# NerdvanaTaurus_FE.net
KiCad netlist of a schematic drawn in EasyEDA Pro
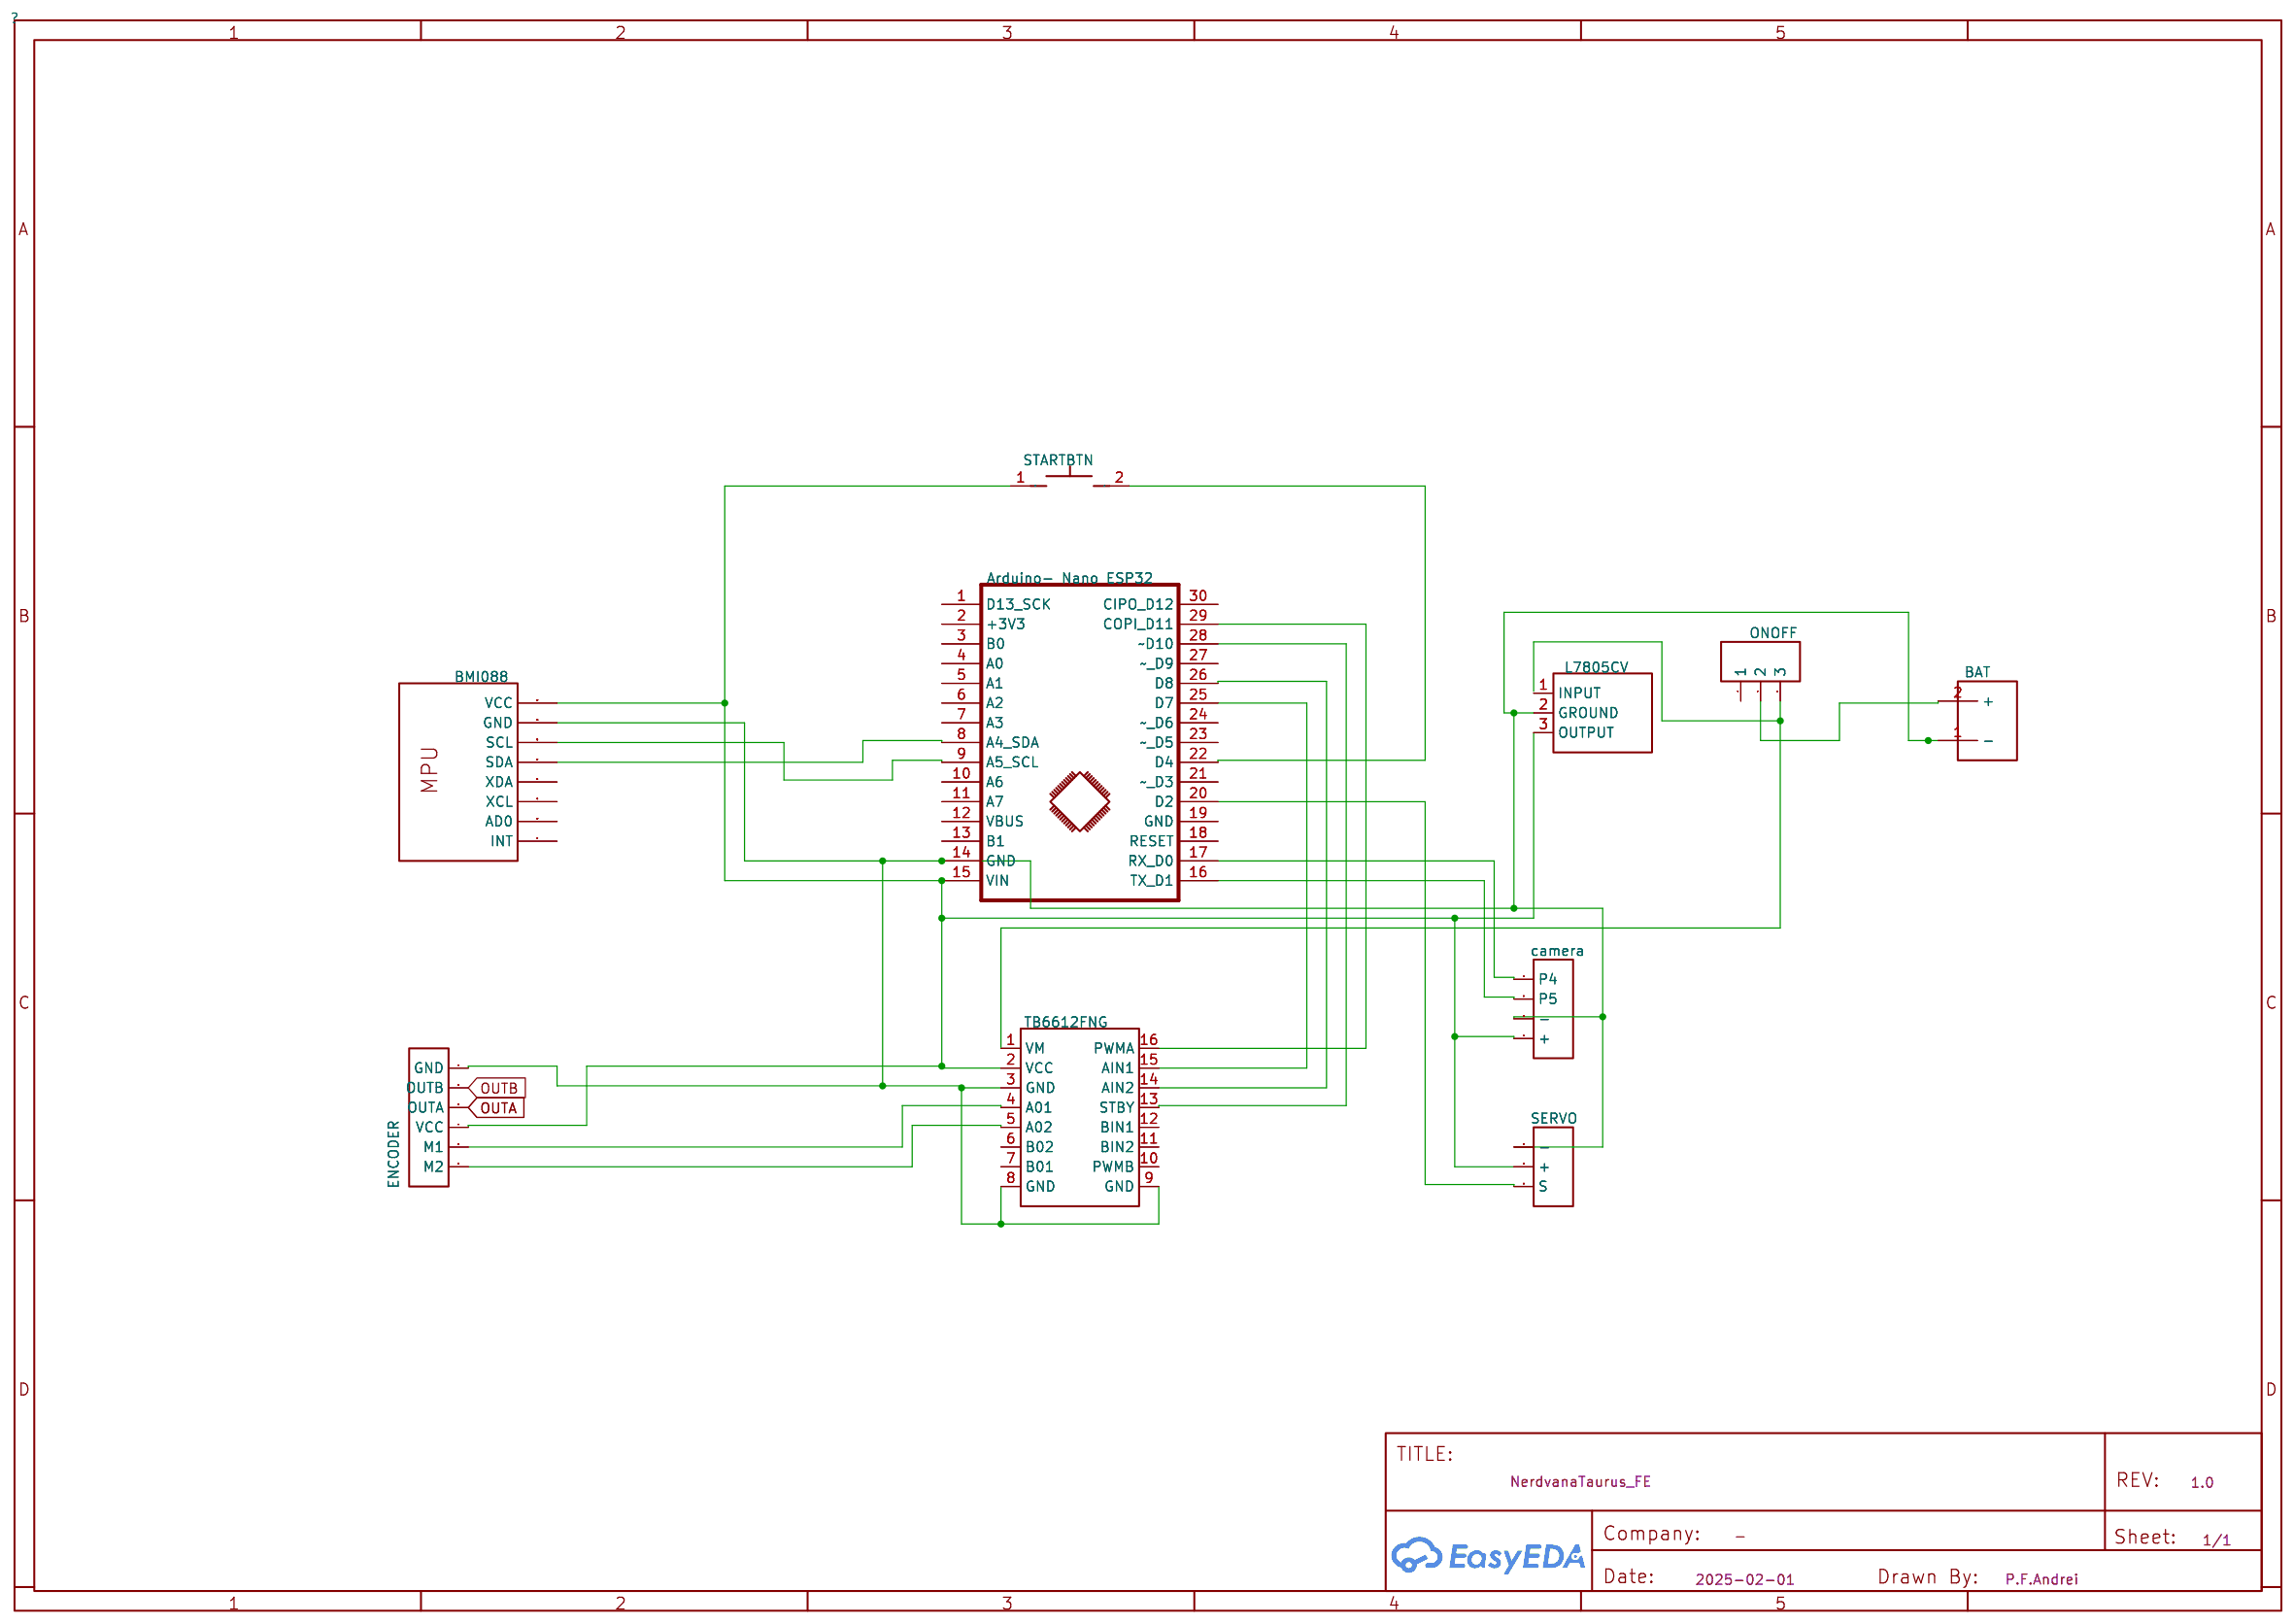
[diagram p0: schematic sheet]

(export (version "E")
  (design (tool "Eeschema 10.0.6"))
  (components
    (comp (ref "BAT1")
      (value "BAT")
      (fields (field (name "Contributor") "OFKLZ"))
      (libsource (lib "easyedapro") (part "BAT"))
    )
    (comp (ref "CAM1")
      (value "camera")
      (fields (field (name "Contributor") "LCEDA_Lib"))
      (libsource (lib "easyedapro") (part "camera"))
    )
    (comp (ref "H1")
      (value "ENCODER")
      (fields (field (name "Contributor") "LCEDA_Lib"))
      (libsource (lib "easyedapro") (part "ENCODER"))
    )
    (comp (ref "L1CV")
      (value "L7805CV")
      (fields (field (name "Manufacturer Part") "L7805CV带散热器") (field (name "Contributor") "LCSC"))
      (libsource (lib "easyedapro") (part "L7805CV"))
    )
    (comp (ref "M2")
      (value "BMI088")
      (fields (field (name "Contributor") "THE AS-Creation"))
      (libsource (lib "easyedapro") (part "MPU6050"))
    )
    (comp (ref "ONOFF1")
      (value "ONOFF")
      (fields (field (name "Contributor") "LCEDA_Lib"))
      (libsource (lib "easyedapro") (part "ONOFF"))
    )
    (comp (ref "SERVO1")
      (value "SERVO")
      (fields (field (name "Contributor") "LCEDA_Lib"))
      (libsource (lib "easyedapro") (part "SERVO"))
    )
    (comp (ref "START1")
      (value "STARTBTN")
      (fields (field (name "Manufacturer Part") "BUTTON2") (field (name "Contributor") "LCSC"))
      (libsource (lib "easyedapro") (part "STARTBTN"))
    )
    (comp (ref "U3")
      (value "Arduino- Nano ESP32")
      (fields
        (field (name "Manufacturer Part") "ABX00092")
        (field (name "Manufacturer") "Arduino")
        (field (name "Contributor") "jbdreamz365")
      )
      (libsource (lib "easyedapro") (part "Arduino® Nano ESP32"))
    )
    (comp (ref "U4")
      (value "TB6612FNG")
      (fields (field (name "Contributor") "sendme2vachan"))
      (libsource (lib "easyedapro") (part "TB6612FNG"))
    )
  )
  (nets
    (net (code "1") (name "Net-(BAT1-+)") (class "Default")
      (node (ref "BAT1") (pin "2") (pinfunction "+_2") (pintype "unspecified"))
      (node (ref "ONOFF1") (pin "2") (pinfunction "2_2") (pintype "input"))
    )
    (net (code "2") (name "Net-(BAT1--)") (class "Default")
      (node (ref "BAT1") (pin "1") (pinfunction "-_1") (pintype "unspecified"))
      (node (ref "CAM1") (pin "3") (pinfunction "-_3") (pintype "unspecified"))
      (node (ref "H1") (pin "1") (pinfunction "GND_1") (pintype "input"))
      (node (ref "L1CV") (pin "2") (pinfunction "GROUND_2") (pintype "unspecified"))
      (node (ref "M2") (pin "GND") (pinfunction "GND_GND") (pintype "unspecified"))
      (node (ref "SERVO1") (pin "1") (pinfunction "-_1") (pintype "input"))
      (node (ref "U3") (pin "14") (pinfunction "GND_14") (pintype "unspecified"))
      (node (ref "U4") (pin "3") (pinfunction "GND_3") (pintype "unspecified"))
      (node (ref "U4") (pin "8") (pinfunction "GND_8") (pintype "unspecified"))
      (node (ref "U4") (pin "9") (pinfunction "GND_9") (pintype "unspecified"))
    )
    (net (code "3") (name "Net-(CAM1-+)") (class "Default")
      (node (ref "CAM1") (pin "4") (pinfunction "+_4") (pintype "unspecified"))
      (node (ref "H1") (pin "4") (pinfunction "VCC_4") (pintype "input"))
      (node (ref "L1CV") (pin "3") (pinfunction "OUTPUT_3") (pintype "unspecified"))
      (node (ref "M2") (pin "VCC") (pinfunction "VCC_VCC") (pintype "unspecified"))
      (node (ref "SERVO1") (pin "2") (pinfunction "+_2") (pintype "input"))
      (node (ref "START1") (pin "1") (pinfunction "1_1") (pintype "unspecified"))
      (node (ref "U3") (pin "15") (pinfunction "VIN_15") (pintype "bidirectional"))
      (node (ref "U4") (pin "2") (pinfunction "VCC_2") (pintype "unspecified"))
    )
    (net (code "4") (name "Net-(CAM1-P4)") (class "Default")
      (node (ref "CAM1") (pin "1") (pinfunction "P4_1") (pintype "unspecified"))
      (node (ref "U3") (pin "17") (pinfunction "RX_D0_17") (pintype "bidirectional"))
    )
    (net (code "5") (name "Net-(CAM1-P5)") (class "Default")
      (node (ref "CAM1") (pin "2") (pinfunction "P5_2") (pintype "unspecified"))
      (node (ref "U3") (pin "16") (pinfunction "TX_D1_16") (pintype "bidirectional"))
    )
    (net (code "6") (name "Net-(H1-M1)") (class "Default")
      (node (ref "H1") (pin "5") (pinfunction "M1_5") (pintype "input"))
      (node (ref "U4") (pin "4") (pinfunction "A01_4") (pintype "unspecified"))
    )
    (net (code "7") (name "Net-(H1-M2)") (class "Default")
      (node (ref "H1") (pin "6") (pinfunction "M2_6") (pintype "input"))
      (node (ref "U4") (pin "5") (pinfunction "A02_5") (pintype "unspecified"))
    )
    (net (code "8") (name "Net-(SERVO1-S)") (class "Default")
      (node (ref "SERVO1") (pin "3") (pinfunction "S_3") (pintype "input"))
      (node (ref "U3") (pin "20") (pinfunction "D2_20") (pintype "bidirectional"))
    )
    (net (code "9") (name "Net-(U3-A4_SDA)") (class "Default")
      (node (ref "M2") (pin "SDA") (pinfunction "SDA_SDA") (pintype "unspecified"))
      (node (ref "U3") (pin "8") (pinfunction "A4_SDA_8") (pintype "bidirectional"))
    )
    (net (code "10") (name "Net-(U3-A5_SCL)") (class "Default")
      (node (ref "M2") (pin "SCL") (pinfunction "SCL_SCL") (pintype "unspecified"))
      (node (ref "U3") (pin "9") (pinfunction "A5_SCL_9") (pintype "bidirectional"))
    )
    (net (code "11") (name "Net-(U3-COPI_D11)") (class "Default")
      (node (ref "U3") (pin "29") (pinfunction "COPI_D11_29") (pintype "bidirectional"))
      (node (ref "U4") (pin "16") (pinfunction "PWMA_16") (pintype "unspecified"))
    )
    (net (code "12") (name "Net-(U3-D4)") (class "Default")
      (node (ref "START1") (pin "2") (pinfunction "2_2") (pintype "unspecified"))
      (node (ref "U3") (pin "22") (pinfunction "D4_22") (pintype "bidirectional"))
    )
    (net (code "13") (name "Net-(U3-D7)") (class "Default")
      (node (ref "U3") (pin "25") (pinfunction "D7_25") (pintype "bidirectional"))
      (node (ref "U4") (pin "15") (pinfunction "AIN1_15") (pintype "unspecified"))
    )
    (net (code "14") (name "Net-(U3-D8)") (class "Default")
      (node (ref "U3") (pin "26") (pinfunction "D8_26") (pintype "bidirectional"))
      (node (ref "U4") (pin "14") (pinfunction "AIN2_14") (pintype "unspecified"))
    )
    (net (code "15") (name "Net-(U3-~D10)") (class "Default")
      (node (ref "U3") (pin "28") (pinfunction "~D10_28") (pintype "bidirectional"))
      (node (ref "U4") (pin "13") (pinfunction "STBY_13") (pintype "unspecified"))
    )
    (net (code "16") (name "Net-(U4-VM)") (class "Default")
      (node (ref "ONOFF1") (pin "3") (pinfunction "3_3") (pintype "input"))
      (node (ref "U4") (pin "1") (pinfunction "VM_1") (pintype "unspecified"))
    )
    (net (code "17") (name "OUTA") (class "Default")
      (node (ref "H1") (pin "3") (pinfunction "OUTA_3") (pintype "input"))
    )
    (net (code "18") (name "OUTB") (class "Default")
      (node (ref "H1") (pin "2") (pinfunction "OUTB_2") (pintype "input"))
    )
    (net (code "19") (name "unconnected-(L1CV-INPUT-Pad1)") (class "Default")
      (node (ref "L1CV") (pin "1") (pinfunction "INPUT_1") (pintype "unspecified"))
    )
    (net (code "20") (name "unconnected-(M2-PadAD0)") (class "Default")
      (node (ref "M2") (pin "AD0") (pinfunction "AD0_AD0") (pintype "unspecified"))
    )
    (net (code "21") (name "unconnected-(M2-PadINT)") (class "Default")
      (node (ref "M2") (pin "INT") (pinfunction "INT_INT") (pintype "unspecified"))
    )
    (net (code "22") (name "unconnected-(M2-PadXCL)") (class "Default")
      (node (ref "M2") (pin "XCL") (pinfunction "XCL_XCL") (pintype "unspecified"))
    )
    (net (code "23") (name "unconnected-(M2-PadXDA)") (class "Default")
      (node (ref "M2") (pin "XDA") (pinfunction "XDA_XDA") (pintype "unspecified"))
    )
    (net (code "24") (name "unconnected-(ONOFF1-Pad1)") (class "Default")
      (node (ref "ONOFF1") (pin "1") (pinfunction "1_1") (pintype "input"))
    )
    (net (code "25") (name "unconnected-(U3-+3V3-Pad2)") (class "Default")
      (node (ref "U3") (pin "2") (pinfunction "+3V3_2") (pintype "unspecified"))
    )
    (net (code "26") (name "unconnected-(U3-A0-Pad4)") (class "Default")
      (node (ref "U3") (pin "4") (pinfunction "A0_4") (pintype "bidirectional"))
    )
    (net (code "27") (name "unconnected-(U3-A1-Pad5)") (class "Default")
      (node (ref "U3") (pin "5") (pinfunction "A1_5") (pintype "bidirectional"))
    )
    (net (code "28") (name "unconnected-(U3-A2-Pad6)") (class "Default")
      (node (ref "U3") (pin "6") (pinfunction "A2_6") (pintype "bidirectional"))
    )
    (net (code "29") (name "unconnected-(U3-A3-Pad7)") (class "Default")
      (node (ref "U3") (pin "7") (pinfunction "A3_7") (pintype "bidirectional"))
    )
    (net (code "30") (name "unconnected-(U3-A6-Pad10)") (class "Default")
      (node (ref "U3") (pin "10") (pinfunction "A6_10") (pintype "bidirectional"))
    )
    (net (code "31") (name "unconnected-(U3-A7-Pad11)") (class "Default")
      (node (ref "U3") (pin "11") (pinfunction "A7_11") (pintype "bidirectional"))
    )
    (net (code "32") (name "unconnected-(U3-B0-Pad3)") (class "Default")
      (node (ref "U3") (pin "3") (pinfunction "B0_3") (pintype "bidirectional"))
    )
    (net (code "33") (name "unconnected-(U3-B1-Pad13)") (class "Default")
      (node (ref "U3") (pin "13") (pinfunction "B1_13") (pintype "bidirectional"))
    )
    (net (code "34") (name "unconnected-(U3-CIPO_D12-Pad30)") (class "Default")
      (node (ref "U3") (pin "30") (pinfunction "CIPO_D12_30") (pintype "bidirectional"))
    )
    (net (code "35") (name "unconnected-(U3-D13_SCK-Pad1)") (class "Default")
      (node (ref "U3") (pin "1") (pinfunction "D13_SCK_1") (pintype "bidirectional"))
    )
    (net (code "36") (name "unconnected-(U3-GND-Pad19)") (class "Default")
      (node (ref "U3") (pin "19") (pinfunction "GND_19") (pintype "unspecified"))
    )
    (net (code "37") (name "unconnected-(U3-RESET-Pad18)") (class "Default")
      (node (ref "U3") (pin "18") (pinfunction "RESET_18") (pintype "bidirectional"))
    )
    (net (code "38") (name "unconnected-(U3-VBUS-Pad12)") (class "Default")
      (node (ref "U3") (pin "12") (pinfunction "VBUS_12") (pintype "unspecified"))
    )
    (net (code "39") (name "unconnected-(U3-~_D3-Pad21)") (class "Default")
      (node (ref "U3") (pin "21") (pinfunction "~_D3_21") (pintype "bidirectional"))
    )
    (net (code "40") (name "unconnected-(U3-~_D5-Pad23)") (class "Default")
      (node (ref "U3") (pin "23") (pinfunction "~_D5_23") (pintype "bidirectional"))
    )
    (net (code "41") (name "unconnected-(U3-~_D6-Pad24)") (class "Default")
      (node (ref "U3") (pin "24") (pinfunction "~_D6_24") (pintype "bidirectional"))
    )
    (net (code "42") (name "unconnected-(U3-~_D9-Pad27)") (class "Default")
      (node (ref "U3") (pin "27") (pinfunction "~_D9_27") (pintype "bidirectional"))
    )
    (net (code "43") (name "unconnected-(U4-B01-Pad7)") (class "Default")
      (node (ref "U4") (pin "7") (pinfunction "B01_7") (pintype "unspecified"))
    )
    (net (code "44") (name "unconnected-(U4-B02-Pad6)") (class "Default")
      (node (ref "U4") (pin "6") (pinfunction "B02_6") (pintype "unspecified"))
    )
    (net (code "45") (name "unconnected-(U4-BIN1-Pad12)") (class "Default")
      (node (ref "U4") (pin "12") (pinfunction "BIN1_12") (pintype "unspecified"))
    )
    (net (code "46") (name "unconnected-(U4-BIN2-Pad11)") (class "Default")
      (node (ref "U4") (pin "11") (pinfunction "BIN2_11") (pintype "unspecified"))
    )
    (net (code "47") (name "unconnected-(U4-PWMB-Pad10)") (class "Default")
      (node (ref "U4") (pin "10") (pinfunction "PWMB_10") (pintype "unspecified"))
    )
  )
)
